# HD-JYQ70-YD03-MAIN.net
KiCad netlist of a schematic drawn in Altium Designer
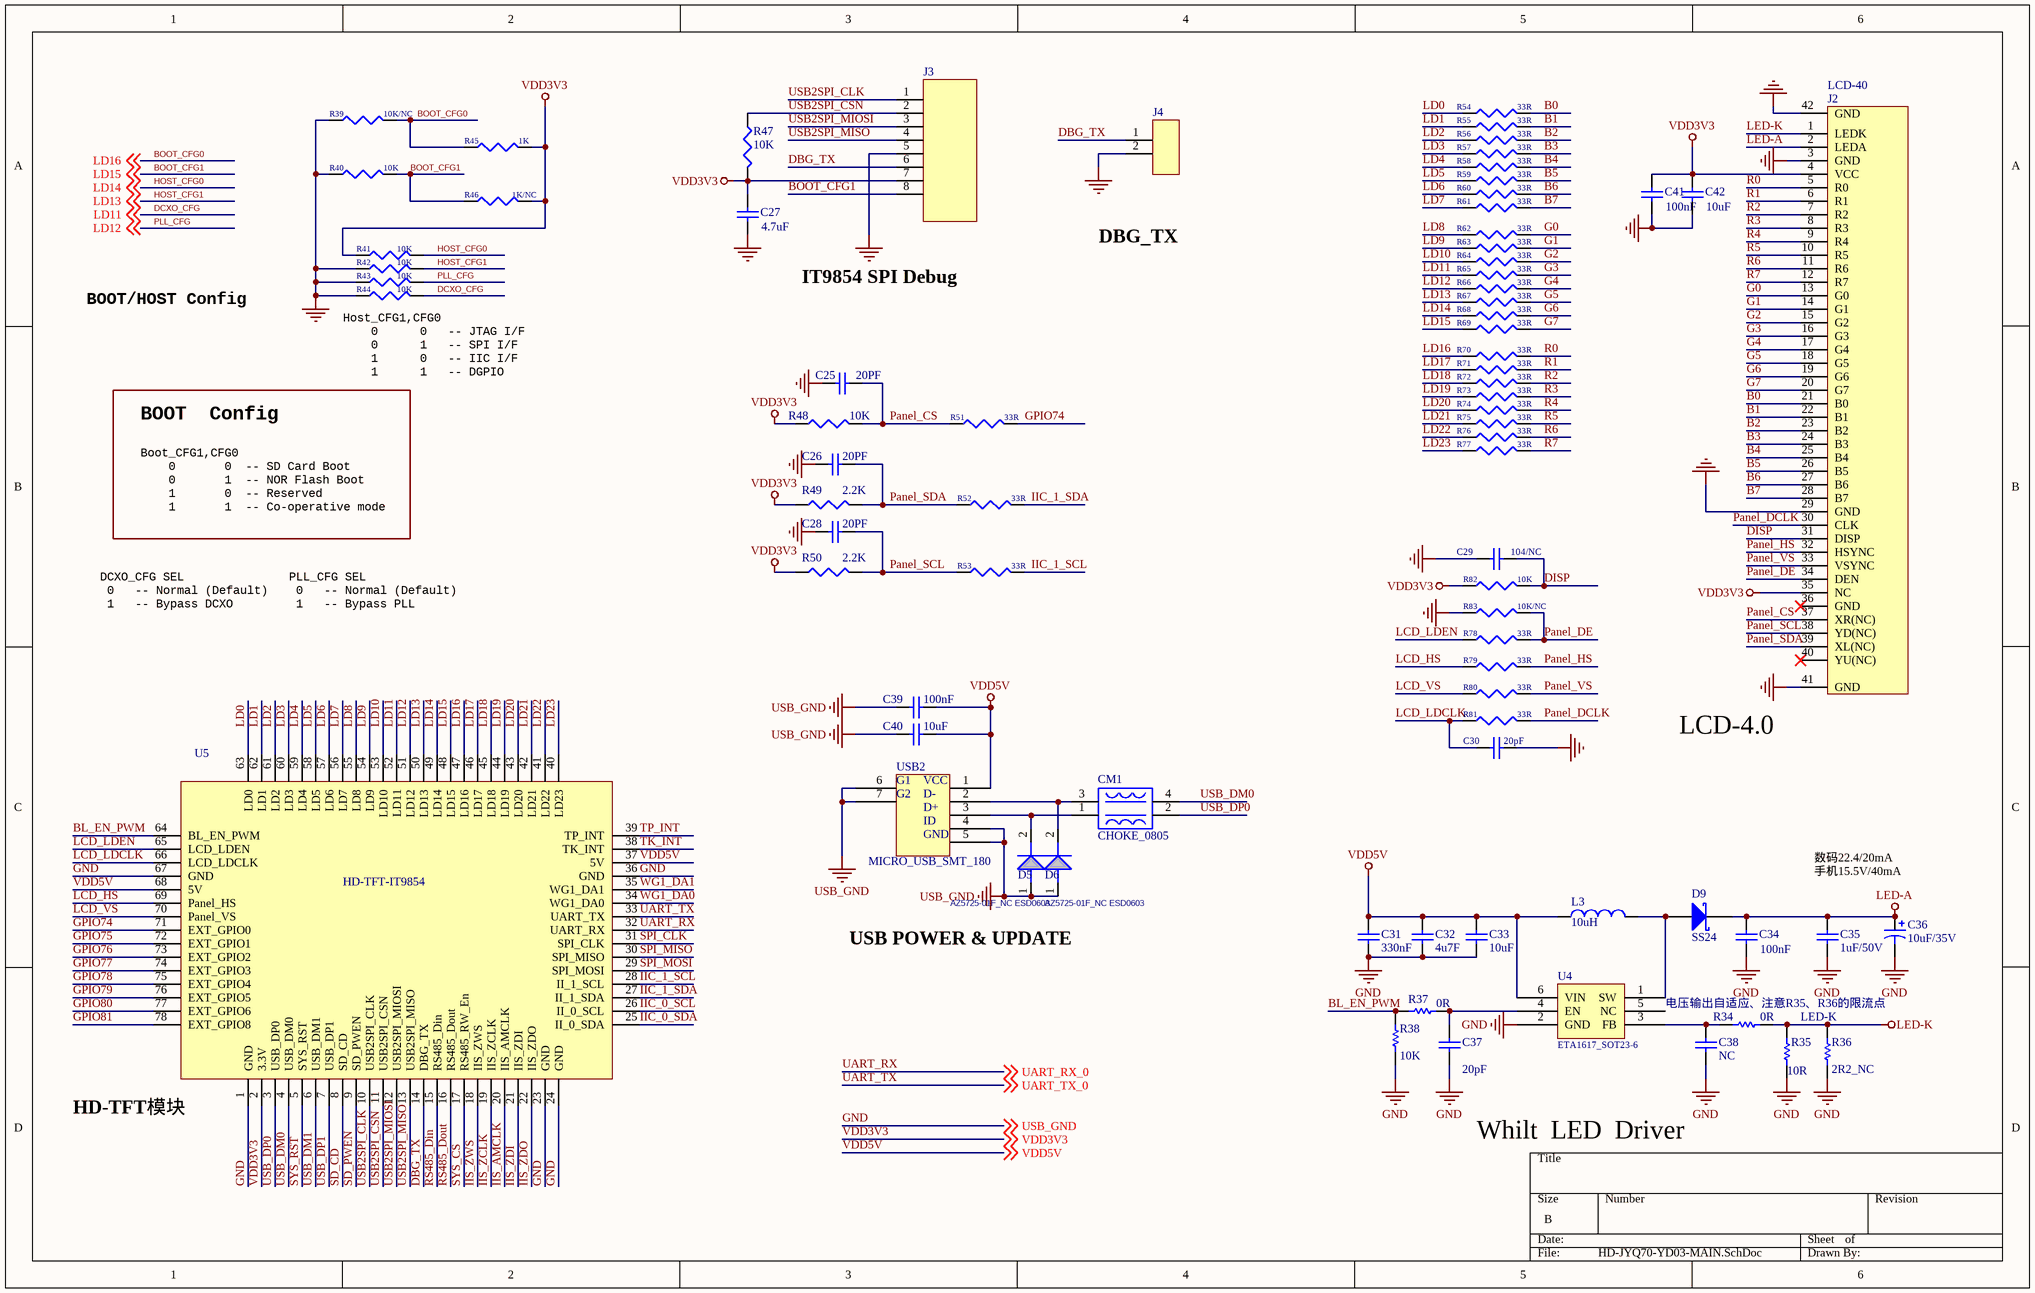
[diagram p0: HD-JYQ70-YD03-MAIN.SchDoc]

(export (version "E")
  (design (tool "Eeschema 10.0.6"))
  (components
    (comp (ref "C25")
      (value "20PF")
      (footprint "X-0603C")
      (description "Capacitor")
      (fields (field (name "Comment") "Cap") (field (name "PUBLISHER") "Altium Limited"))
      (libsource (lib "Miscellaneous Devices") (part "Cap"))
    )
    (comp (ref "C26")
      (value "20PF")
      (footprint "X-0603C")
      (description "Capacitor")
      (fields (field (name "Comment") "Cap") (field (name "PUBLISHER") "Altium Limited"))
      (libsource (lib "Miscellaneous Devices") (part "Cap"))
    )
    (comp (ref "C27")
      (value "4.7uF")
      (footprint "X-0603C")
      (description "Capacitor")
      (fields (field (name "Comment") "Cap") (field (name "PUBLISHER") "Altium Limited"))
      (libsource (lib "Miscellaneous Devices") (part "Cap"))
    )
    (comp (ref "C28")
      (value "20PF")
      (footprint "X-0603C")
      (description "Capacitor")
      (fields (field (name "Comment") "Cap") (field (name "PUBLISHER") "Altium Limited"))
      (libsource (lib "Miscellaneous Devices") (part "Cap"))
    )
    (comp (ref "C29")
      (value "104/NC")
      (footprint "X-0603C")
      (description "Capacitor (Semiconductor SIM Model)")
      (fields (field (name "Comment") "Cap Semi") (field (name "PUBLISHER") "Altium Limited"))
      (libsource (lib "Miscellaneous Devices") (part "Cap Semi"))
    )
    (comp (ref "C30")
      (value "20pF")
      (footprint "X-0603C")
      (description "Capacitor (Semiconductor SIM Model)")
      (fields (field (name "Comment") "Cap Semi") (field (name "PUBLISHER") "Altium Limited"))
      (libsource (lib "Miscellaneous Devices") (part "Cap Semi"))
    )
    (comp (ref "C31")
      (value "330nF")
      (footprint "X-0603C")
      (description "Capacitor")
      (fields (field (name "PUBLISHER") "Altium Limited"))
      (libsource (lib "Miscellaneous Devices") (part "Cap"))
    )
    (comp (ref "C32")
      (value "4u7F")
      (footprint "X-0603C")
      (description "Capacitor")
      (fields (field (name "PUBLISHER") "Altium Limited"))
      (libsource (lib "Miscellaneous Devices") (part "Cap"))
    )
    (comp (ref "C33")
      (value "10uF")
      (footprint "X-0603C")
      (description "Capacitor")
      (fields (field (name "PUBLISHER") "Altium Limited"))
      (libsource (lib "Miscellaneous Devices") (part "Cap"))
    )
    (comp (ref "C34")
      (value "100nF")
      (footprint "X-0603C")
      (description "Capacitor")
      (fields (field (name "PUBLISHER") "Altium Limited"))
      (libsource (lib "Miscellaneous Devices") (part "Cap"))
    )
    (comp (ref "C35")
      (value "1uF/50V")
      (footprint "X-0603C")
      (description "Capacitor")
      (fields (field (name "PUBLISHER") "Altium Limited"))
      (libsource (lib "Miscellaneous Devices") (part "Cap"))
    )
    (comp (ref "C36")
      (value "10uF/35V")
      (footprint "H-1206C")
      (description "Polarized Capacitor (Radial)")
      (fields (field (name "PUBLISHER") "Altium Limited"))
      (libsource (lib "Miscellaneous Devices") (part "Cap Pol1"))
    )
    (comp (ref "C37")
      (value "20pF")
      (footprint "X-0603C")
      (description "Capacitor")
      (fields (field (name "Comment") "Cap") (field (name "PUBLISHER") "Altium Limited"))
      (libsource (lib "Miscellaneous Devices") (part "Cap"))
    )
    (comp (ref "C38")
      (value "NC")
      (footprint "X-0603C")
      (description "Capacitor")
      (fields (field (name "PUBLISHER") "Altium Limited"))
      (libsource (lib "Miscellaneous Devices") (part "Cap"))
    )
    (comp (ref "C39")
      (value "100nF")
      (footprint "X-0603C")
      (description "Capacitor (Semiconductor SIM Model)")
      (fields (field (name "Comment") "Cap Semi") (field (name "PUBLISHER") "Altium Limited"))
      (libsource (lib "Miscellaneous Devices") (part "Cap Semi"))
    )
    (comp (ref "C40")
      (value "10uF")
      (footprint "X-0603C")
      (description "Capacitor (Semiconductor SIM Model)")
      (fields (field (name "Comment") "Cap Semi") (field (name "PUBLISHER") "Altium Limited"))
      (libsource (lib "Miscellaneous Devices") (part "Cap Semi"))
    )
    (comp (ref "C41")
      (value "100nF")
      (footprint "X-0603C")
      (description "Capacitor (Semiconductor SIM Model)")
      (fields (field (name "Comment") "Cap Semi") (field (name "PUBLISHER") "Altium Limited"))
      (libsource (lib "Miscellaneous Devices") (part "Cap Semi"))
    )
    (comp (ref "C42")
      (value "10uF")
      (footprint "X-0603C")
      (description "Capacitor (Semiconductor SIM Model)")
      (fields (field (name "Comment") "Cap Semi") (field (name "PUBLISHER") "Altium Limited"))
      (libsource (lib "Miscellaneous Devices") (part "Cap Semi"))
    )
    (comp (ref "CM1")
      (value "CHOKE_0805")
      (footprint "CHOKE_0805")
      (libsource (lib "DHX") (part "CHOKE_0805"))
    )
    (comp (ref "D5")
      (value "AZ5725-01F_NC ESD0603")
      (footprint "D0603")
      (libsource (lib "DEMO_IT9852SDK_V02_B_Library") (part "DIODE_2"))
    )
    (comp (ref "D6")
      (value "AZ5725-01F_NC ESD0603")
      (footprint "D0603")
      (libsource (lib "DEMO_IT9852SDK_V02_B_Library") (part "DIODE_2"))
    )
    (comp (ref "D9")
      (value "SS24")
      (footprint "H-DIODE_SMA")
      (description "Schottky Rectifier")
      (fields (field (name "PUBLISHER") "Altium Limited"))
      (libsource (lib "Miscellaneous Devices") (part "Diode 11DQ03"))
    )
    (comp (ref "J2") (value "LCD-40") (footprint "FPC-05-40P-R") (libsource (lib "DHX") (part "CON42")))
    (comp (ref "J3")
      (value "CON15_1")
      (footprint "HEADER8X1$2F$2.54")
      (libsource (lib "DHX") (part "CON15_1"))
    )
    (comp (ref "J4") (value "CON2") (footprint "HEADER2X1$2F$2.54") (libsource (lib "DHX") (part "CON2")))
    (comp (ref "L3")
      (value "10uH")
      (footprint "ZAD-6045")
      (description "Inductor")
      (fields (field (name "PUBLISHER") "Altium Limited"))
      (libsource (lib "Miscellaneous Devices") (part "Inductor"))
    )
    (comp (ref "R34")
      (value "0R")
      (footprint "X-0603R")
      (description "Resistor")
      (fields (field (name "Comment") "Res1") (field (name "PUBLISHER") "Altium Limited"))
      (libsource (lib "Miscellaneous Devices") (part "Res1"))
    )
    (comp (ref "R35")
      (value "10R")
      (footprint "X-0603R")
      (description "Resistor")
      (fields (field (name "Comment") "Res1") (field (name "PUBLISHER") "Altium Limited"))
      (libsource (lib "Miscellaneous Devices") (part "Res1"))
    )
    (comp (ref "R36")
      (value "2R2_NC")
      (footprint "X-0603R")
      (description "Resistor")
      (fields (field (name "Comment") "Res1") (field (name "PUBLISHER") "Altium Limited"))
      (libsource (lib "Miscellaneous Devices") (part "Res1"))
    )
    (comp (ref "R37")
      (value "0R")
      (footprint "X-0603R")
      (description "Resistor")
      (fields (field (name "Comment") "Res1") (field (name "PUBLISHER") "Altium Limited"))
      (libsource (lib "Miscellaneous Devices") (part "Res1"))
    )
    (comp (ref "R38")
      (value "10K")
      (footprint "X-0603R")
      (description "Resistor")
      (fields (field (name "Comment") "Res1") (field (name "PUBLISHER") "Altium Limited"))
      (libsource (lib "Miscellaneous Devices") (part "Res1"))
    )
    (comp (ref "R39")
      (value "10K/NC")
      (footprint "X-0603R")
      (description "Resistor")
      (fields (field (name "Comment") "10K") (field (name "PUBLISHER") "Altium Limited"))
      (libsource (lib "Miscellaneous Devices") (part "Res3"))
    )
    (comp (ref "R40")
      (value "10K")
      (footprint "X-0603R")
      (description "Resistor")
      (fields (field (name "PUBLISHER") "Altium Limited"))
      (libsource (lib "Miscellaneous Devices") (part "Res3"))
    )
    (comp (ref "R41")
      (value "10K")
      (footprint "X-0603R")
      (description "Resistor")
      (fields (field (name "PUBLISHER") "Altium Limited"))
      (libsource (lib "Miscellaneous Devices") (part "Res3"))
    )
    (comp (ref "R42")
      (value "10K")
      (footprint "X-0603R")
      (description "Resistor")
      (fields (field (name "PUBLISHER") "Altium Limited"))
      (libsource (lib "Miscellaneous Devices") (part "Res3"))
    )
    (comp (ref "R43")
      (value "10K")
      (footprint "X-0603R")
      (description "Resistor")
      (fields (field (name "PUBLISHER") "Altium Limited"))
      (libsource (lib "Miscellaneous Devices") (part "Res3"))
    )
    (comp (ref "R44")
      (value "10K")
      (footprint "X-0603R")
      (description "Resistor")
      (fields (field (name "PUBLISHER") "Altium Limited"))
      (libsource (lib "Miscellaneous Devices") (part "Res3"))
    )
    (comp (ref "R45")
      (value "1K")
      (footprint "X-0603R")
      (description "Resistor")
      (fields (field (name "Comment") "10K") (field (name "PUBLISHER") "Altium Limited"))
      (libsource (lib "Miscellaneous Devices") (part "Res3"))
    )
    (comp (ref "R46")
      (value "1K/NC")
      (footprint "X-0603R")
      (description "Resistor")
      (fields (field (name "Comment") "10K") (field (name "PUBLISHER") "Altium Limited"))
      (libsource (lib "Miscellaneous Devices") (part "Res3"))
    )
    (comp (ref "R47")
      (value "10K")
      (footprint "X-0603R")
      (description "Resistor")
      (fields (field (name "PUBLISHER") "Altium Limited"))
      (libsource (lib "Miscellaneous Devices") (part "Res3"))
    )
    (comp (ref "R48")
      (value "10K")
      (footprint "X-0603R")
      (description "Resistor")
      (fields (field (name "PUBLISHER") "Altium Limited"))
      (libsource (lib "Miscellaneous Devices") (part "Res3"))
    )
    (comp (ref "R49")
      (value "2.2K")
      (footprint "X-0603R")
      (description "Resistor")
      (fields (field (name "Comment") "10K") (field (name "PUBLISHER") "Altium Limited"))
      (libsource (lib "Miscellaneous Devices") (part "Res3"))
    )
    (comp (ref "R50")
      (value "2.2K")
      (footprint "X-0603R")
      (description "Resistor")
      (fields (field (name "Comment") "10K") (field (name "PUBLISHER") "Altium Limited"))
      (libsource (lib "Miscellaneous Devices") (part "Res3"))
    )
    (comp (ref "R51")
      (value "33R")
      (footprint "X-0603R")
      (description "Resistor")
      (fields (field (name "Comment") "10K") (field (name "PUBLISHER") "Altium Limited"))
      (libsource (lib "Miscellaneous Devices") (part "Res3"))
    )
    (comp (ref "R52")
      (value "33R")
      (footprint "X-0603R")
      (description "Resistor")
      (fields (field (name "Comment") "10K") (field (name "PUBLISHER") "Altium Limited"))
      (libsource (lib "Miscellaneous Devices") (part "Res3"))
    )
    (comp (ref "R53")
      (value "33R")
      (footprint "X-0603R")
      (description "Resistor")
      (fields (field (name "Comment") "10K") (field (name "PUBLISHER") "Altium Limited"))
      (libsource (lib "Miscellaneous Devices") (part "Res3"))
    )
    (comp (ref "R54")
      (value "33R")
      (footprint "X-0603R")
      (description "Resistor")
      (fields (field (name "Comment") "10K") (field (name "PUBLISHER") "Altium Limited"))
      (libsource (lib "Miscellaneous Devices") (part "Res3"))
    )
    (comp (ref "R55")
      (value "33R")
      (footprint "X-0603R")
      (description "Resistor")
      (fields (field (name "Comment") "10K") (field (name "PUBLISHER") "Altium Limited"))
      (libsource (lib "Miscellaneous Devices") (part "Res3"))
    )
    (comp (ref "R56")
      (value "33R")
      (footprint "X-0603R")
      (description "Resistor")
      (fields (field (name "Comment") "10K") (field (name "PUBLISHER") "Altium Limited"))
      (libsource (lib "Miscellaneous Devices") (part "Res3"))
    )
    (comp (ref "R57")
      (value "33R")
      (footprint "X-0603R")
      (description "Resistor")
      (fields (field (name "Comment") "10K") (field (name "PUBLISHER") "Altium Limited"))
      (libsource (lib "Miscellaneous Devices") (part "Res3"))
    )
    (comp (ref "R58")
      (value "33R")
      (footprint "X-0603R")
      (description "Resistor")
      (fields (field (name "Comment") "10K") (field (name "PUBLISHER") "Altium Limited"))
      (libsource (lib "Miscellaneous Devices") (part "Res3"))
    )
    (comp (ref "R59")
      (value "33R")
      (footprint "X-0603R")
      (description "Resistor")
      (fields (field (name "Comment") "10K") (field (name "PUBLISHER") "Altium Limited"))
      (libsource (lib "Miscellaneous Devices") (part "Res3"))
    )
    (comp (ref "R60")
      (value "33R")
      (footprint "X-0603R")
      (description "Resistor")
      (fields (field (name "Comment") "10K") (field (name "PUBLISHER") "Altium Limited"))
      (libsource (lib "Miscellaneous Devices") (part "Res3"))
    )
    (comp (ref "R61")
      (value "33R")
      (footprint "X-0603R")
      (description "Resistor")
      (fields (field (name "Comment") "10K") (field (name "PUBLISHER") "Altium Limited"))
      (libsource (lib "Miscellaneous Devices") (part "Res3"))
    )
    (comp (ref "R62")
      (value "33R")
      (footprint "X-0603R")
      (description "Resistor")
      (fields (field (name "Comment") "10K") (field (name "PUBLISHER") "Altium Limited"))
      (libsource (lib "Miscellaneous Devices") (part "Res3"))
    )
    (comp (ref "R63")
      (value "33R")
      (footprint "X-0603R")
      (description "Resistor")
      (fields (field (name "Comment") "10K") (field (name "PUBLISHER") "Altium Limited"))
      (libsource (lib "Miscellaneous Devices") (part "Res3"))
    )
    (comp (ref "R64")
      (value "33R")
      (footprint "X-0603R")
      (description "Resistor")
      (fields (field (name "Comment") "10K") (field (name "PUBLISHER") "Altium Limited"))
      (libsource (lib "Miscellaneous Devices") (part "Res3"))
    )
    (comp (ref "R65")
      (value "33R")
      (footprint "X-0603R")
      (description "Resistor")
      (fields (field (name "Comment") "10K") (field (name "PUBLISHER") "Altium Limited"))
      (libsource (lib "Miscellaneous Devices") (part "Res3"))
    )
    (comp (ref "R66")
      (value "33R")
      (footprint "X-0603R")
      (description "Resistor")
      (fields (field (name "Comment") "10K") (field (name "PUBLISHER") "Altium Limited"))
      (libsource (lib "Miscellaneous Devices") (part "Res3"))
    )
    (comp (ref "R67")
      (value "33R")
      (footprint "X-0603R")
      (description "Resistor")
      (fields (field (name "Comment") "10K") (field (name "PUBLISHER") "Altium Limited"))
      (libsource (lib "Miscellaneous Devices") (part "Res3"))
    )
    (comp (ref "R68")
      (value "33R")
      (footprint "X-0603R")
      (description "Resistor")
      (fields (field (name "Comment") "10K") (field (name "PUBLISHER") "Altium Limited"))
      (libsource (lib "Miscellaneous Devices") (part "Res3"))
    )
    (comp (ref "R69")
      (value "33R")
      (footprint "X-0603R")
      (description "Resistor")
      (fields (field (name "Comment") "10K") (field (name "PUBLISHER") "Altium Limited"))
      (libsource (lib "Miscellaneous Devices") (part "Res3"))
    )
    (comp (ref "R70")
      (value "33R")
      (footprint "X-0603R")
      (description "Resistor")
      (fields (field (name "Comment") "10K") (field (name "PUBLISHER") "Altium Limited"))
      (libsource (lib "Miscellaneous Devices") (part "Res3"))
    )
    (comp (ref "R71")
      (value "33R")
      (footprint "X-0603R")
      (description "Resistor")
      (fields (field (name "Comment") "10K") (field (name "PUBLISHER") "Altium Limited"))
      (libsource (lib "Miscellaneous Devices") (part "Res3"))
    )
    (comp (ref "R72")
      (value "33R")
      (footprint "X-0603R")
      (description "Resistor")
      (fields (field (name "Comment") "10K") (field (name "PUBLISHER") "Altium Limited"))
      (libsource (lib "Miscellaneous Devices") (part "Res3"))
    )
    (comp (ref "R73")
      (value "33R")
      (footprint "X-0603R")
      (description "Resistor")
      (fields (field (name "Comment") "10K") (field (name "PUBLISHER") "Altium Limited"))
      (libsource (lib "Miscellaneous Devices") (part "Res3"))
    )
    (comp (ref "R74")
      (value "33R")
      (footprint "X-0603R")
      (description "Resistor")
      (fields (field (name "Comment") "10K") (field (name "PUBLISHER") "Altium Limited"))
      (libsource (lib "Miscellaneous Devices") (part "Res3"))
    )
    (comp (ref "R75")
      (value "33R")
      (footprint "X-0603R")
      (description "Resistor")
      (fields (field (name "Comment") "10K") (field (name "PUBLISHER") "Altium Limited"))
      (libsource (lib "Miscellaneous Devices") (part "Res3"))
    )
    (comp (ref "R76")
      (value "33R")
      (footprint "X-0603R")
      (description "Resistor")
      (fields (field (name "Comment") "10K") (field (name "PUBLISHER") "Altium Limited"))
      (libsource (lib "Miscellaneous Devices") (part "Res3"))
    )
    (comp (ref "R77")
      (value "33R")
      (footprint "X-0603R")
      (description "Resistor")
      (fields (field (name "Comment") "10K") (field (name "PUBLISHER") "Altium Limited"))
      (libsource (lib "Miscellaneous Devices") (part "Res3"))
    )
    (comp (ref "R78")
      (value "33R")
      (footprint "X-0603R")
      (description "Resistor")
      (fields (field (name "Comment") "10K") (field (name "PUBLISHER") "Altium Limited"))
      (libsource (lib "Miscellaneous Devices") (part "Res3"))
    )
    (comp (ref "R79")
      (value "33R")
      (footprint "X-0603R")
      (description "Resistor")
      (fields (field (name "Comment") "10K") (field (name "PUBLISHER") "Altium Limited"))
      (libsource (lib "Miscellaneous Devices") (part "Res3"))
    )
    (comp (ref "R80")
      (value "33R")
      (footprint "X-0603R")
      (description "Resistor")
      (fields (field (name "Comment") "10K") (field (name "PUBLISHER") "Altium Limited"))
      (libsource (lib "Miscellaneous Devices") (part "Res3"))
    )
    (comp (ref "R81")
      (value "33R")
      (footprint "X-0603R")
      (description "Resistor")
      (fields (field (name "Comment") "10K") (field (name "PUBLISHER") "Altium Limited"))
      (libsource (lib "Miscellaneous Devices") (part "Res3"))
    )
    (comp (ref "R82")
      (value "10K")
      (footprint "X-0603R")
      (description "Resistor")
      (fields (field (name "PUBLISHER") "Altium Limited"))
      (libsource (lib "Miscellaneous Devices") (part "Res3"))
    )
    (comp (ref "R83")
      (value "10K/NC")
      (footprint "X-0603R")
      (description "Resistor")
      (fields (field (name "Comment") "10K") (field (name "PUBLISHER") "Altium Limited"))
      (libsource (lib "Miscellaneous Devices") (part "Res3"))
    )
    (comp (ref "U4")
      (value "ETA1617_SOT23-6")
      (footprint "TSOT26-6P$2F$0.95$2F$3X3")
      (libsource (lib "U9") (part "Component_1"))
    )
    (comp (ref "U5")
      (value "HD-TFT-IT9854")
      (footprint "HD-TFT-IT9854")
      (libsource (lib "DHX") (part "HD-TFT-IT9854"))
    )
    (comp (ref "USB2")
      (value "MICRO_USB_SMT_180")
      (footprint "MICRO_USB_SMT_180")
      (libsource (lib "E663AHE_TFT") (part "USB"))
    )
  )
  (nets
    (net (code "1") (name "/B0") (class "Default")
      (node (ref "J2") (pin "21") (pinfunction "B0_21") (pintype "passive"))
      (node (ref "R54") (pin "2") (pinfunction "2_2") (pintype "passive"))
    )
    (net (code "2") (name "/B1") (class "Default")
      (node (ref "J2") (pin "22") (pinfunction "B1_22") (pintype "passive"))
      (node (ref "R55") (pin "2") (pinfunction "2_2") (pintype "passive"))
    )
    (net (code "3") (name "/B2") (class "Default")
      (node (ref "J2") (pin "23") (pinfunction "B2_23") (pintype "passive"))
      (node (ref "R56") (pin "2") (pinfunction "2_2") (pintype "passive"))
    )
    (net (code "4") (name "/B3") (class "Default")
      (node (ref "J2") (pin "24") (pinfunction "B3_24") (pintype "passive"))
      (node (ref "R57") (pin "2") (pinfunction "2_2") (pintype "passive"))
    )
    (net (code "5") (name "/B4") (class "Default")
      (node (ref "J2") (pin "25") (pinfunction "B4_25") (pintype "passive"))
      (node (ref "R58") (pin "2") (pinfunction "2_2") (pintype "passive"))
    )
    (net (code "6") (name "/B5") (class "Default")
      (node (ref "J2") (pin "26") (pinfunction "B5_26") (pintype "passive"))
      (node (ref "R59") (pin "2") (pinfunction "2_2") (pintype "passive"))
    )
    (net (code "7") (name "/B6") (class "Default")
      (node (ref "J2") (pin "27") (pinfunction "B6_27") (pintype "passive"))
      (node (ref "R60") (pin "2") (pinfunction "2_2") (pintype "passive"))
    )
    (net (code "8") (name "/B7") (class "Default")
      (node (ref "J2") (pin "28") (pinfunction "B7_28") (pintype "passive"))
      (node (ref "R61") (pin "2") (pinfunction "2_2") (pintype "passive"))
    )
    (net (code "9") (name "/BL_EN_PWM") (class "Default")
      (node (ref "R37") (pin "1") (pinfunction "1_1") (pintype "passive"))
      (node (ref "R38") (pin "2") (pinfunction "2_2") (pintype "passive"))
      (node (ref "U5") (pin "64") (pinfunction "BL_EN_PWM_64") (pintype "passive"))
    )
    (net (code "10") (name "/DBG_TX") (class "Default")
      (node (ref "J3") (pin "6") (pinfunction "6_6") (pintype "passive"))
      (node (ref "J4") (pin "1") (pinfunction "1_1") (pintype "passive"))
      (node (ref "U5") (pin "14") (pinfunction "DBG_TX_14") (pintype "passive"))
    )
    (net (code "11") (name "/DISP") (class "Default")
      (node (ref "C29") (pin "2") (pinfunction "2_2") (pintype "passive"))
      (node (ref "J2") (pin "31") (pinfunction "DISP_31") (pintype "passive"))
      (node (ref "R82") (pin "2") (pinfunction "2_2") (pintype "passive"))
    )
    (net (code "12") (name "/G0") (class "Default")
      (node (ref "J2") (pin "13") (pinfunction "G0_13") (pintype "passive"))
      (node (ref "R62") (pin "2") (pinfunction "2_2") (pintype "passive"))
    )
    (net (code "13") (name "/G1") (class "Default")
      (node (ref "J2") (pin "14") (pinfunction "G1_14") (pintype "passive"))
      (node (ref "R63") (pin "2") (pinfunction "2_2") (pintype "passive"))
    )
    (net (code "14") (name "/G2") (class "Default")
      (node (ref "J2") (pin "15") (pinfunction "G2_15") (pintype "passive"))
      (node (ref "R64") (pin "2") (pinfunction "2_2") (pintype "passive"))
    )
    (net (code "15") (name "/G3") (class "Default")
      (node (ref "J2") (pin "16") (pinfunction "G3_16") (pintype "passive"))
      (node (ref "R65") (pin "2") (pinfunction "2_2") (pintype "passive"))
    )
    (net (code "16") (name "/G4") (class "Default")
      (node (ref "J2") (pin "17") (pinfunction "G4_17") (pintype "passive"))
      (node (ref "R66") (pin "2") (pinfunction "2_2") (pintype "passive"))
    )
    (net (code "17") (name "/G5") (class "Default")
      (node (ref "J2") (pin "18") (pinfunction "G5_18") (pintype "passive"))
      (node (ref "R67") (pin "2") (pinfunction "2_2") (pintype "passive"))
    )
    (net (code "18") (name "/G6") (class "Default")
      (node (ref "J2") (pin "19") (pinfunction "G6_19") (pintype "passive"))
      (node (ref "R68") (pin "2") (pinfunction "2_2") (pintype "passive"))
    )
    (net (code "19") (name "/G7") (class "Default")
      (node (ref "J2") (pin "20") (pinfunction "G7_20") (pintype "passive"))
      (node (ref "R69") (pin "2") (pinfunction "2_2") (pintype "passive"))
    )
    (net (code "20") (name "/GPIO74") (class "Default")
      (node (ref "R51") (pin "2") (pinfunction "2_2") (pintype "passive"))
      (node (ref "U5") (pin "71") (pinfunction "EXT_GPIO0_71") (pintype "passive"))
    )
    (net (code "21") (name "/GPIO75") (class "Default")
      (node (ref "U5") (pin "72") (pinfunction "EXT_GPIO1_72") (pintype "passive"))
    )
    (net (code "22") (name "/GPIO76") (class "Default")
      (node (ref "U5") (pin "73") (pinfunction "EXT_GPIO2_73") (pintype "passive"))
    )
    (net (code "23") (name "/GPIO77") (class "Default")
      (node (ref "U5") (pin "74") (pinfunction "EXT_GPIO3_74") (pintype "passive"))
    )
    (net (code "24") (name "/GPIO78") (class "Default")
      (node (ref "U5") (pin "75") (pinfunction "EXT_GPIO4_75") (pintype "passive"))
    )
    (net (code "25") (name "/GPIO79") (class "Default")
      (node (ref "U5") (pin "76") (pinfunction "EXT_GPIO5_76") (pintype "passive"))
    )
    (net (code "26") (name "/GPIO80") (class "Default")
      (node (ref "U5") (pin "77") (pinfunction "EXT_GPIO6_77") (pintype "passive"))
    )
    (net (code "27") (name "/GPIO81") (class "Default")
      (node (ref "U5") (pin "78") (pinfunction "EXT_GPIO8_78") (pintype "passive"))
    )
    (net (code "28") (name "/IIC_0_SCL") (class "Default")
      (node (ref "U5") (pin "26") (pinfunction "II_0_SCL_26") (pintype "passive"))
    )
    (net (code "29") (name "/IIC_0_SDA") (class "Default")
      (node (ref "U5") (pin "25") (pinfunction "II_0_SDA_25") (pintype "passive"))
    )
    (net (code "30") (name "/IIC_1_SCL") (class "Default")
      (node (ref "R53") (pin "2") (pinfunction "2_2") (pintype "passive"))
      (node (ref "U5") (pin "28") (pinfunction "II_1_SCL_28") (pintype "passive"))
    )
    (net (code "31") (name "/IIC_1_SDA") (class "Default")
      (node (ref "R52") (pin "2") (pinfunction "2_2") (pintype "passive"))
      (node (ref "U5") (pin "27") (pinfunction "II_1_SDA_27") (pintype "passive"))
    )
    (net (code "32") (name "/IIS_AMCLK") (class "Default")
      (node (ref "U5") (pin "20") (pinfunction "IIS_AMCLK_20") (pintype "passive"))
    )
    (net (code "33") (name "/IIS_ZCLK") (class "Default")
      (node (ref "U5") (pin "19") (pinfunction "IIS_ZCLK_19") (pintype "passive"))
    )
    (net (code "34") (name "/IIS_ZDI") (class "Default")
      (node (ref "U5") (pin "21") (pinfunction "IIS_ZDI_21") (pintype "passive"))
    )
    (net (code "35") (name "/IIS_ZDO") (class "Default")
      (node (ref "U5") (pin "22") (pinfunction "IIS_ZDO_22") (pintype "passive"))
    )
    (net (code "36") (name "/IIS_ZWS") (class "Default")
      (node (ref "U5") (pin "18") (pinfunction "IIS_ZWS_18") (pintype "passive"))
    )
    (net (code "37") (name "/LCD_HS") (class "Default")
      (node (ref "R79") (pin "1") (pinfunction "1_1") (pintype "passive"))
      (node (ref "U5") (pin "69") (pinfunction "Panel_HS_69") (pintype "passive"))
    )
    (net (code "38") (name "/LCD_LDCLK") (class "Default")
      (node (ref "C30") (pin "2") (pinfunction "2_2") (pintype "passive"))
      (node (ref "R81") (pin "1") (pinfunction "1_1") (pintype "passive"))
      (node (ref "U5") (pin "66") (pinfunction "LCD_LDCLK_66") (pintype "passive"))
    )
    (net (code "39") (name "/LCD_LDEN") (class "Default")
      (node (ref "R78") (pin "1") (pinfunction "1_1") (pintype "passive"))
      (node (ref "U5") (pin "65") (pinfunction "LCD_LDEN_65") (pintype "passive"))
    )
    (net (code "40") (name "/LCD_VS") (class "Default")
      (node (ref "R80") (pin "1") (pinfunction "1_1") (pintype "passive"))
      (node (ref "U5") (pin "70") (pinfunction "Panel_VS_70") (pintype "passive"))
    )
    (net (code "41") (name "/LD0") (class "Default")
      (node (ref "R54") (pin "1") (pinfunction "1_1") (pintype "passive"))
      (node (ref "U5") (pin "63") (pinfunction "LD0_63") (pintype "passive"))
    )
    (net (code "42") (name "/LD1") (class "Default")
      (node (ref "R55") (pin "1") (pinfunction "1_1") (pintype "passive"))
      (node (ref "U5") (pin "62") (pinfunction "LD1_62") (pintype "passive"))
    )
    (net (code "43") (name "/LD2") (class "Default")
      (node (ref "R56") (pin "1") (pinfunction "1_1") (pintype "passive"))
      (node (ref "U5") (pin "61") (pinfunction "LD2_61") (pintype "passive"))
    )
    (net (code "44") (name "/LD3") (class "Default")
      (node (ref "R57") (pin "1") (pinfunction "1_1") (pintype "passive"))
      (node (ref "U5") (pin "60") (pinfunction "LD3_60") (pintype "passive"))
    )
    (net (code "45") (name "/LD4") (class "Default")
      (node (ref "R58") (pin "1") (pinfunction "1_1") (pintype "passive"))
      (node (ref "U5") (pin "59") (pinfunction "LD4_59") (pintype "passive"))
    )
    (net (code "46") (name "/LD5") (class "Default")
      (node (ref "R59") (pin "1") (pinfunction "1_1") (pintype "passive"))
      (node (ref "U5") (pin "58") (pinfunction "LD5_58") (pintype "passive"))
    )
    (net (code "47") (name "/LD6") (class "Default")
      (node (ref "R60") (pin "1") (pinfunction "1_1") (pintype "passive"))
      (node (ref "U5") (pin "57") (pinfunction "LD6_57") (pintype "passive"))
    )
    (net (code "48") (name "/LD7") (class "Default")
      (node (ref "R61") (pin "1") (pinfunction "1_1") (pintype "passive"))
      (node (ref "U5") (pin "56") (pinfunction "LD7_56") (pintype "passive"))
    )
    (net (code "49") (name "/LD8") (class "Default")
      (node (ref "R62") (pin "1") (pinfunction "1_1") (pintype "passive"))
      (node (ref "U5") (pin "55") (pinfunction "LD8_55") (pintype "passive"))
    )
    (net (code "50") (name "/LD9") (class "Default")
      (node (ref "R63") (pin "1") (pinfunction "1_1") (pintype "passive"))
      (node (ref "U5") (pin "54") (pinfunction "LD9_54") (pintype "passive"))
    )
    (net (code "51") (name "/LD10") (class "Default")
      (node (ref "R64") (pin "1") (pinfunction "1_1") (pintype "passive"))
      (node (ref "U5") (pin "53") (pinfunction "LD10_53") (pintype "passive"))
    )
    (net (code "52") (name "/LD17") (class "Default")
      (node (ref "R71") (pin "1") (pinfunction "1_1") (pintype "passive"))
      (node (ref "U5") (pin "46") (pinfunction "LD17_46") (pintype "passive"))
    )
    (net (code "53") (name "/LD18") (class "Default")
      (node (ref "R72") (pin "1") (pinfunction "1_1") (pintype "passive"))
      (node (ref "U5") (pin "45") (pinfunction "LD18_45") (pintype "passive"))
    )
    (net (code "54") (name "/LD19") (class "Default")
      (node (ref "R73") (pin "1") (pinfunction "1_1") (pintype "passive"))
      (node (ref "U5") (pin "44") (pinfunction "LD19_44") (pintype "passive"))
    )
    (net (code "55") (name "/LD20") (class "Default")
      (node (ref "R74") (pin "1") (pinfunction "1_1") (pintype "passive"))
      (node (ref "U5") (pin "43") (pinfunction "LD20_43") (pintype "passive"))
    )
    (net (code "56") (name "/LD21") (class "Default")
      (node (ref "R75") (pin "1") (pinfunction "1_1") (pintype "passive"))
      (node (ref "U5") (pin "42") (pinfunction "LD21_42") (pintype "passive"))
    )
    (net (code "57") (name "/LD22") (class "Default")
      (node (ref "R76") (pin "1") (pinfunction "1_1") (pintype "passive"))
      (node (ref "U5") (pin "41") (pinfunction "LD22_41") (pintype "passive"))
    )
    (net (code "58") (name "/LD23") (class "Default")
      (node (ref "R77") (pin "1") (pinfunction "1_1") (pintype "passive"))
      (node (ref "U5") (pin "40") (pinfunction "LD23_40") (pintype "passive"))
    )
    (net (code "59") (name "/Panel_CS") (class "Default")
      (node (ref "C25") (pin "2") (pinfunction "2_2") (pintype "passive"))
      (node (ref "J2") (pin "37") (pinfunction "XR(NC)_37") (pintype "passive"))
      (node (ref "R48") (pin "2") (pinfunction "2_2") (pintype "passive"))
      (node (ref "R51") (pin "1") (pinfunction "1_1") (pintype "passive"))
    )
    (net (code "60") (name "/Panel_DCLK") (class "Default")
      (node (ref "J2") (pin "30") (pinfunction "CLK_30") (pintype "passive"))
      (node (ref "R81") (pin "2") (pinfunction "2_2") (pintype "passive"))
    )
    (net (code "61") (name "/Panel_DE") (class "Default")
      (node (ref "J2") (pin "34") (pinfunction "DEN_34") (pintype "passive"))
      (node (ref "R78") (pin "2") (pinfunction "2_2") (pintype "passive"))
      (node (ref "R83") (pin "2") (pinfunction "2_2") (pintype "passive"))
    )
    (net (code "62") (name "/Panel_HS") (class "Default")
      (node (ref "J2") (pin "32") (pinfunction "HSYNC_32") (pintype "passive"))
      (node (ref "R79") (pin "2") (pinfunction "2_2") (pintype "passive"))
    )
    (net (code "63") (name "/Panel_SCL") (class "Default")
      (node (ref "C28") (pin "2") (pinfunction "2_2") (pintype "passive"))
      (node (ref "J2") (pin "38") (pinfunction "YD(NC)_38") (pintype "passive"))
      (node (ref "R50") (pin "2") (pinfunction "2_2") (pintype "passive"))
      (node (ref "R53") (pin "1") (pinfunction "1_1") (pintype "passive"))
    )
    (net (code "64") (name "/Panel_SDA") (class "Default")
      (node (ref "C26") (pin "2") (pinfunction "2_2") (pintype "passive"))
      (node (ref "J2") (pin "39") (pinfunction "XL(NC)_39") (pintype "passive"))
      (node (ref "R49") (pin "2") (pinfunction "2_2") (pintype "passive"))
      (node (ref "R52") (pin "1") (pinfunction "1_1") (pintype "passive"))
    )
    (net (code "65") (name "/Panel_VS") (class "Default")
      (node (ref "J2") (pin "33") (pinfunction "VSYNC_33") (pintype "passive"))
      (node (ref "R80") (pin "2") (pinfunction "2_2") (pintype "passive"))
    )
    (net (code "66") (name "/R0") (class "Default")
      (node (ref "J2") (pin "5") (pinfunction "R0_5") (pintype "passive"))
      (node (ref "R70") (pin "2") (pinfunction "2_2") (pintype "passive"))
    )
    (net (code "67") (name "/R1") (class "Default")
      (node (ref "J2") (pin "6") (pinfunction "R1_6") (pintype "passive"))
      (node (ref "R71") (pin "2") (pinfunction "2_2") (pintype "passive"))
    )
    (net (code "68") (name "/R2") (class "Default")
      (node (ref "J2") (pin "7") (pinfunction "R2_7") (pintype "passive"))
      (node (ref "R72") (pin "2") (pinfunction "2_2") (pintype "passive"))
    )
    (net (code "69") (name "/R3") (class "Default")
      (node (ref "J2") (pin "8") (pinfunction "R3_8") (pintype "passive"))
      (node (ref "R73") (pin "2") (pinfunction "2_2") (pintype "passive"))
    )
    (net (code "70") (name "/R4") (class "Default")
      (node (ref "J2") (pin "9") (pinfunction "R4_9") (pintype "passive"))
      (node (ref "R74") (pin "2") (pinfunction "2_2") (pintype "passive"))
    )
    (net (code "71") (name "/R5") (class "Default")
      (node (ref "J2") (pin "10") (pinfunction "R5_10") (pintype "passive"))
      (node (ref "R75") (pin "2") (pinfunction "2_2") (pintype "passive"))
    )
    (net (code "72") (name "/R6") (class "Default")
      (node (ref "J2") (pin "11") (pinfunction "R6_11") (pintype "passive"))
      (node (ref "R76") (pin "2") (pinfunction "2_2") (pintype "passive"))
    )
    (net (code "73") (name "/R7") (class "Default")
      (node (ref "J2") (pin "12") (pinfunction "R7_12") (pintype "passive"))
      (node (ref "R77") (pin "2") (pinfunction "2_2") (pintype "passive"))
    )
    (net (code "74") (name "/RS485_Din") (class "Default")
      (node (ref "U5") (pin "15") (pinfunction "RS485_Din_15") (pintype "passive"))
    )
    (net (code "75") (name "/RS485_Dout") (class "Default")
      (node (ref "U5") (pin "16") (pinfunction "RS485_Dout_16") (pintype "passive"))
    )
    (net (code "76") (name "/SD_CD") (class "Default")
      (node (ref "U5") (pin "8") (pinfunction "SD_CD_8") (pintype "passive"))
    )
    (net (code "77") (name "/SD_PWEN") (class "Default")
      (node (ref "U5") (pin "9") (pinfunction "SD_PWEN_9") (pintype "passive"))
    )
    (net (code "78") (name "/SPI_CLK") (class "Default")
      (node (ref "U5") (pin "31") (pinfunction "SPI_CLK_31") (pintype "passive"))
    )
    (net (code "79") (name "/SPI_MISO") (class "Default")
      (node (ref "U5") (pin "30") (pinfunction "SPI_MISO_30") (pintype "passive"))
    )
    (net (code "80") (name "/SPI_MOSI") (class "Default")
      (node (ref "U5") (pin "29") (pinfunction "SPI_MOSI_29") (pintype "passive"))
    )
    (net (code "81") (name "/SYS_CS") (class "Default")
      (node (ref "U5") (pin "17") (pinfunction "RS485_RW_En_17") (pintype "passive"))
    )
    (net (code "82") (name "/SYS_RST") (class "Default")
      (node (ref "U5") (pin "5") (pinfunction "SYS_RST_5") (pintype "passive"))
    )
    (net (code "83") (name "/TK_INT") (class "Default")
      (node (ref "U5") (pin "38") (pinfunction "TK_INT_38") (pintype "passive"))
    )
    (net (code "84") (name "/TP_INT") (class "Default")
      (node (ref "U5") (pin "39") (pinfunction "TP_INT_39") (pintype "passive"))
    )
    (net (code "85") (name "/USB2SPI_CLK") (class "Default")
      (node (ref "J3") (pin "1") (pinfunction "1_1") (pintype "passive"))
      (node (ref "U5") (pin "10") (pinfunction "USB2SPI_CLK_10") (pintype "passive"))
    )
    (net (code "86") (name "/USB2SPI_CSN") (class "Default")
      (node (ref "J3") (pin "2") (pinfunction "2_2") (pintype "passive"))
      (node (ref "R47") (pin "1") (pinfunction "1_1") (pintype "passive"))
      (node (ref "U5") (pin "11") (pinfunction "USB2SPI_CSN_11") (pintype "passive"))
    )
    (net (code "87") (name "/USB2SPI_MIOSI") (class "Default")
      (node (ref "J3") (pin "3") (pinfunction "3_3") (pintype "passive"))
      (node (ref "U5") (pin "12") (pinfunction "USB2SPI_MIOSI_12") (pintype "passive"))
    )
    (net (code "88") (name "/USB2SPI_MISO") (class "Default")
      (node (ref "J3") (pin "4") (pinfunction "4_4") (pintype "passive"))
      (node (ref "U5") (pin "13") (pinfunction "USB2SPI_MISO_13") (pintype "passive"))
    )
    (net (code "89") (name "/USB_DM0") (class "Default")
      (node (ref "CM1") (pin "4") (pinfunction "KC_4") (pintype "passive"))
      (node (ref "U5") (pin "4") (pinfunction "USB_DM0_4") (pintype "passive"))
    )
    (net (code "90") (name "/USB_DM1") (class "Default")
      (node (ref "U5") (pin "6") (pinfunction "USB_DM1_6") (pintype "passive"))
    )
    (net (code "91") (name "/USB_DP0") (class "Default")
      (node (ref "CM1") (pin "2") (pinfunction "KC_2") (pintype "passive"))
      (node (ref "U5") (pin "3") (pinfunction "USB_DP0_3") (pintype "passive"))
    )
    (net (code "92") (name "/USB_DP1") (class "Default")
      (node (ref "U5") (pin "7") (pinfunction "USB_DP1_7") (pintype "passive"))
    )
    (net (code "93") (name "/WG1_DA0") (class "Default")
      (node (ref "U5") (pin "34") (pinfunction "WG1_DA0_34") (pintype "passive"))
    )
    (net (code "94") (name "/WG1_DA1") (class "Default")
      (node (ref "U5") (pin "35") (pinfunction "WG1_DA1_35") (pintype "passive"))
    )
    (net (code "95") (name "GND") (class "Default")
      (node (ref "C25") (pin "1") (pinfunction "1_1") (pintype "passive"))
      (node (ref "C26") (pin "1") (pinfunction "1_1") (pintype "passive"))
      (node (ref "C27") (pin "1") (pinfunction "1_1") (pintype "passive"))
      (node (ref "C28") (pin "1") (pinfunction "1_1") (pintype "passive"))
      (node (ref "C29") (pin "1") (pinfunction "1_1") (pintype "passive"))
      (node (ref "C30") (pin "1") (pinfunction "1_1") (pintype "passive"))
      (node (ref "C31") (pin "1") (pinfunction "1_1") (pintype "passive"))
      (node (ref "C32") (pin "1") (pinfunction "1_1") (pintype "passive"))
      (node (ref "C33") (pin "1") (pinfunction "1_1") (pintype "passive"))
      (node (ref "C34") (pin "1") (pinfunction "1_1") (pintype "passive"))
      (node (ref "C35") (pin "1") (pinfunction "1_1") (pintype "passive"))
      (node (ref "C36") (pin "2") (pinfunction "2_2") (pintype "passive"))
      (node (ref "C37") (pin "1") (pinfunction "1_1") (pintype "passive"))
      (node (ref "C38") (pin "1") (pinfunction "1_1") (pintype "passive"))
      (node (ref "C39") (pin "1") (pinfunction "1_1") (pintype "passive"))
      (node (ref "C40") (pin "1") (pinfunction "1_1") (pintype "passive"))
      (node (ref "C41") (pin "1") (pinfunction "1_1") (pintype "passive"))
      (node (ref "C42") (pin "1") (pinfunction "1_1") (pintype "passive"))
      (node (ref "D5") (pin "1") (pinfunction "ANODE_1") (pintype "passive"))
      (node (ref "D6") (pin "1") (pinfunction "ANODE_1") (pintype "passive"))
      (node (ref "J2") (pin "29") (pinfunction "GND_29") (pintype "passive"))
      (node (ref "J2") (pin "3") (pinfunction "GND_3") (pintype "passive"))
      (node (ref "J2") (pin "41") (pinfunction "GND_41") (pintype "passive"))
      (node (ref "J2") (pin "42") (pinfunction "GND_42") (pintype "passive"))
      (node (ref "J3") (pin "5") (pinfunction "5_5") (pintype "passive"))
      (node (ref "J4") (pin "2") (pinfunction "2_2") (pintype "passive"))
      (node (ref "R35") (pin "2") (pinfunction "2_2") (pintype "passive"))
      (node (ref "R36") (pin "2") (pinfunction "2_2") (pintype "passive"))
      (node (ref "R38") (pin "1") (pinfunction "1_1") (pintype "passive"))
      (node (ref "R39") (pin "1") (pinfunction "1_1") (pintype "passive"))
      (node (ref "R40") (pin "1") (pinfunction "1_1") (pintype "passive"))
      (node (ref "R42") (pin "1") (pinfunction "1_1") (pintype "passive"))
      (node (ref "R43") (pin "1") (pinfunction "1_1") (pintype "passive"))
      (node (ref "R44") (pin "1") (pinfunction "1_1") (pintype "passive"))
      (node (ref "R83") (pin "1") (pinfunction "1_1") (pintype "passive"))
      (node (ref "U4") (pin "2") (pinfunction "GND_2") (pintype "passive"))
      (node (ref "U5") (pin "1") (pinfunction "GND_1") (pintype "passive"))
      (node (ref "U5") (pin "23") (pinfunction "GND_23") (pintype "passive"))
      (node (ref "U5") (pin "24") (pinfunction "GND_24") (pintype "passive"))
      (node (ref "U5") (pin "36") (pinfunction "GND_36") (pintype "passive"))
      (node (ref "U5") (pin "67") (pinfunction "GND_67") (pintype "passive"))
      (node (ref "USB2") (pin "4") (pinfunction "D-_4") (pintype "passive"))
      (node (ref "USB2") (pin "5") (pinfunction "D-_5") (pintype "passive"))
      (node (ref "USB2") (pin "6") (pinfunction "D-_6") (pintype "passive"))
      (node (ref "USB2") (pin "7") (pinfunction "D-_7") (pintype "passive"))
    )
    (net (code "96") (name "LD11") (class "Default")
      (node (ref "R44") (pin "2") (pinfunction "2_2") (pintype "passive"))
      (node (ref "R65") (pin "1") (pinfunction "1_1") (pintype "passive"))
      (node (ref "U5") (pin "52") (pinfunction "LD11_52") (pintype "passive"))
    )
    (net (code "97") (name "LD12") (class "Default")
      (node (ref "R43") (pin "2") (pinfunction "2_2") (pintype "passive"))
      (node (ref "R66") (pin "1") (pinfunction "1_1") (pintype "passive"))
      (node (ref "U5") (pin "51") (pinfunction "LD12_51") (pintype "passive"))
    )
    (net (code "98") (name "LD13") (class "Default")
      (node (ref "R42") (pin "2") (pinfunction "2_2") (pintype "passive"))
      (node (ref "R67") (pin "1") (pinfunction "1_1") (pintype "passive"))
      (node (ref "U5") (pin "50") (pinfunction "LD13_50") (pintype "passive"))
    )
    (net (code "99") (name "LD14") (class "Default")
      (node (ref "R41") (pin "2") (pinfunction "2_2") (pintype "passive"))
      (node (ref "R68") (pin "1") (pinfunction "1_1") (pintype "passive"))
      (node (ref "U5") (pin "49") (pinfunction "LD14_49") (pintype "passive"))
    )
    (net (code "100") (name "LD15") (class "Default")
      (node (ref "J3") (pin "8") (pinfunction "8_8") (pintype "passive"))
      (node (ref "R40") (pin "2") (pinfunction "2_2") (pintype "passive"))
      (node (ref "R46") (pin "1") (pinfunction "1_1") (pintype "passive"))
      (node (ref "R69") (pin "1") (pinfunction "1_1") (pintype "passive"))
      (node (ref "U5") (pin "48") (pinfunction "LD15_48") (pintype "passive"))
    )
    (net (code "101") (name "LD16") (class "Default")
      (node (ref "R39") (pin "2") (pinfunction "2_2") (pintype "passive"))
      (node (ref "R45") (pin "1") (pinfunction "1_1") (pintype "passive"))
      (node (ref "R70") (pin "1") (pinfunction "1_1") (pintype "passive"))
      (node (ref "U5") (pin "47") (pinfunction "LD16_47") (pintype "passive"))
    )
    (net (code "102") (name "LED-A") (class "Default")
      (node (ref "C34") (pin "2") (pinfunction "2_2") (pintype "passive"))
      (node (ref "C35") (pin "2") (pinfunction "2_2") (pintype "passive"))
      (node (ref "C36") (pin "1") (pinfunction "1_1") (pintype "passive"))
      (node (ref "D9") (pin "2") (pinfunction "K_2") (pintype "passive"))
      (node (ref "J2") (pin "2") (pinfunction "LEDA_2") (pintype "passive"))
    )
    (net (code "103") (name "LED-K") (class "Default")
      (node (ref "J2") (pin "1") (pinfunction "LEDK_1") (pintype "passive"))
      (node (ref "R34") (pin "1") (pinfunction "1_1") (pintype "passive"))
      (node (ref "R35") (pin "1") (pinfunction "1_1") (pintype "passive"))
      (node (ref "R36") (pin "1") (pinfunction "1_1") (pintype "passive"))
    )
    (net (code "104") (name "Net-(D5-CATHODE)") (class "Default")
      (node (ref "CM1") (pin "1") (pinfunction "KC_1") (pintype "passive"))
      (node (ref "D5") (pin "2") (pinfunction "CATHODE_2") (pintype "passive"))
      (node (ref "USB2") (pin "3") (pinfunction "D-_3") (pintype "passive"))
    )
    (net (code "105") (name "Net-(D6-CATHODE)") (class "Default")
      (node (ref "CM1") (pin "3") (pinfunction "KC_3") (pintype "passive"))
      (node (ref "D6") (pin "2") (pinfunction "CATHODE_2") (pintype "passive"))
      (node (ref "USB2") (pin "2") (pinfunction "D-_2") (pintype "passive"))
    )
    (net (code "106") (name "Net-(D9-A)") (class "Default")
      (node (ref "D9") (pin "1") (pinfunction "A_1") (pintype "passive"))
      (node (ref "L3") (pin "2") (pinfunction "2_2") (pintype "passive"))
      (node (ref "U4") (pin "1") (pinfunction "SW_1") (pintype "passive"))
    )
    (net (code "107") (name "Net-(U4-EN)") (class "Default")
      (node (ref "C37") (pin "2") (pinfunction "2_2") (pintype "passive"))
      (node (ref "R37") (pin "2") (pinfunction "2_2") (pintype "passive"))
      (node (ref "U4") (pin "4") (pinfunction "EN_4") (pintype "passive"))
    )
    (net (code "108") (name "Net-(U4-FB)") (class "Default")
      (node (ref "C38") (pin "2") (pinfunction "2_2") (pintype "passive"))
      (node (ref "R34") (pin "2") (pinfunction "2_2") (pintype "passive"))
      (node (ref "U4") (pin "3") (pinfunction "FB_3") (pintype "passive"))
    )
    (net (code "109") (name "UART_RX_0") (class "Default")
      (node (ref "U5") (pin "32") (pinfunction "UART_RX_32") (pintype "passive"))
    )
    (net (code "110") (name "UART_TX_0") (class "Default")
      (node (ref "U5") (pin "33") (pinfunction "UART_TX_33") (pintype "passive"))
    )
    (net (code "111") (name "VDD3V3") (class "Default")
      (node (ref "C27") (pin "2") (pinfunction "2_2") (pintype "passive"))
      (node (ref "C41") (pin "2") (pinfunction "2_2") (pintype "passive"))
      (node (ref "C42") (pin "2") (pinfunction "2_2") (pintype "passive"))
      (node (ref "J2") (pin "35") (pinfunction "NC_35") (pintype "passive"))
      (node (ref "J2") (pin "4") (pinfunction "VCC_4") (pintype "passive"))
      (node (ref "J3") (pin "7") (pinfunction "7_7") (pintype "passive"))
      (node (ref "R41") (pin "1") (pinfunction "1_1") (pintype "passive"))
      (node (ref "R45") (pin "2") (pinfunction "2_2") (pintype "passive"))
      (node (ref "R46") (pin "2") (pinfunction "2_2") (pintype "passive"))
      (node (ref "R47") (pin "2") (pinfunction "2_2") (pintype "passive"))
      (node (ref "R48") (pin "1") (pinfunction "1_1") (pintype "passive"))
      (node (ref "R49") (pin "1") (pinfunction "1_1") (pintype "passive"))
      (node (ref "R50") (pin "1") (pinfunction "1_1") (pintype "passive"))
      (node (ref "R82") (pin "1") (pinfunction "1_1") (pintype "passive"))
      (node (ref "U5") (pin "2") (pinfunction "3.3V_2") (pintype "passive"))
    )
    (net (code "112") (name "VDD5V") (class "Default")
      (node (ref "C31") (pin "2") (pinfunction "2_2") (pintype "passive"))
      (node (ref "C32") (pin "2") (pinfunction "2_2") (pintype "passive"))
      (node (ref "C33") (pin "2") (pinfunction "2_2") (pintype "passive"))
      (node (ref "C39") (pin "2") (pinfunction "2_2") (pintype "passive"))
      (node (ref "C40") (pin "2") (pinfunction "2_2") (pintype "passive"))
      (node (ref "L3") (pin "1") (pinfunction "1_1") (pintype "passive"))
      (node (ref "U4") (pin "6") (pinfunction "VIN_6") (pintype "passive"))
      (node (ref "U5") (pin "37") (pinfunction "5V_37") (pintype "passive"))
      (node (ref "U5") (pin "68") (pinfunction "5V_68") (pintype "passive"))
      (node (ref "USB2") (pin "1") (pinfunction "VCC_1") (pintype "passive"))
    )
    (net (code "113") (name "unconnected-(J2-GND-Pad36)") (class "Default")
      (node (ref "J2") (pin "36") (pinfunction "GND_36") (pintype "passive+no_connect"))
    )
    (net (code "114") (name "unconnected-(J2-YU(NC)-Pad40)") (class "Default")
      (node (ref "J2") (pin "40") (pinfunction "YU(NC)_40") (pintype "passive+no_connect"))
    )
    (net (code "115") (name "unconnected-(U4-NC-Pad5)") (class "Default")
      (node (ref "U4") (pin "5") (pinfunction "NC_5") (pintype "passive"))
    )
  )
)
